# battery_R1_0.net
KiCad netlist of a schematic drawn in EAGLE
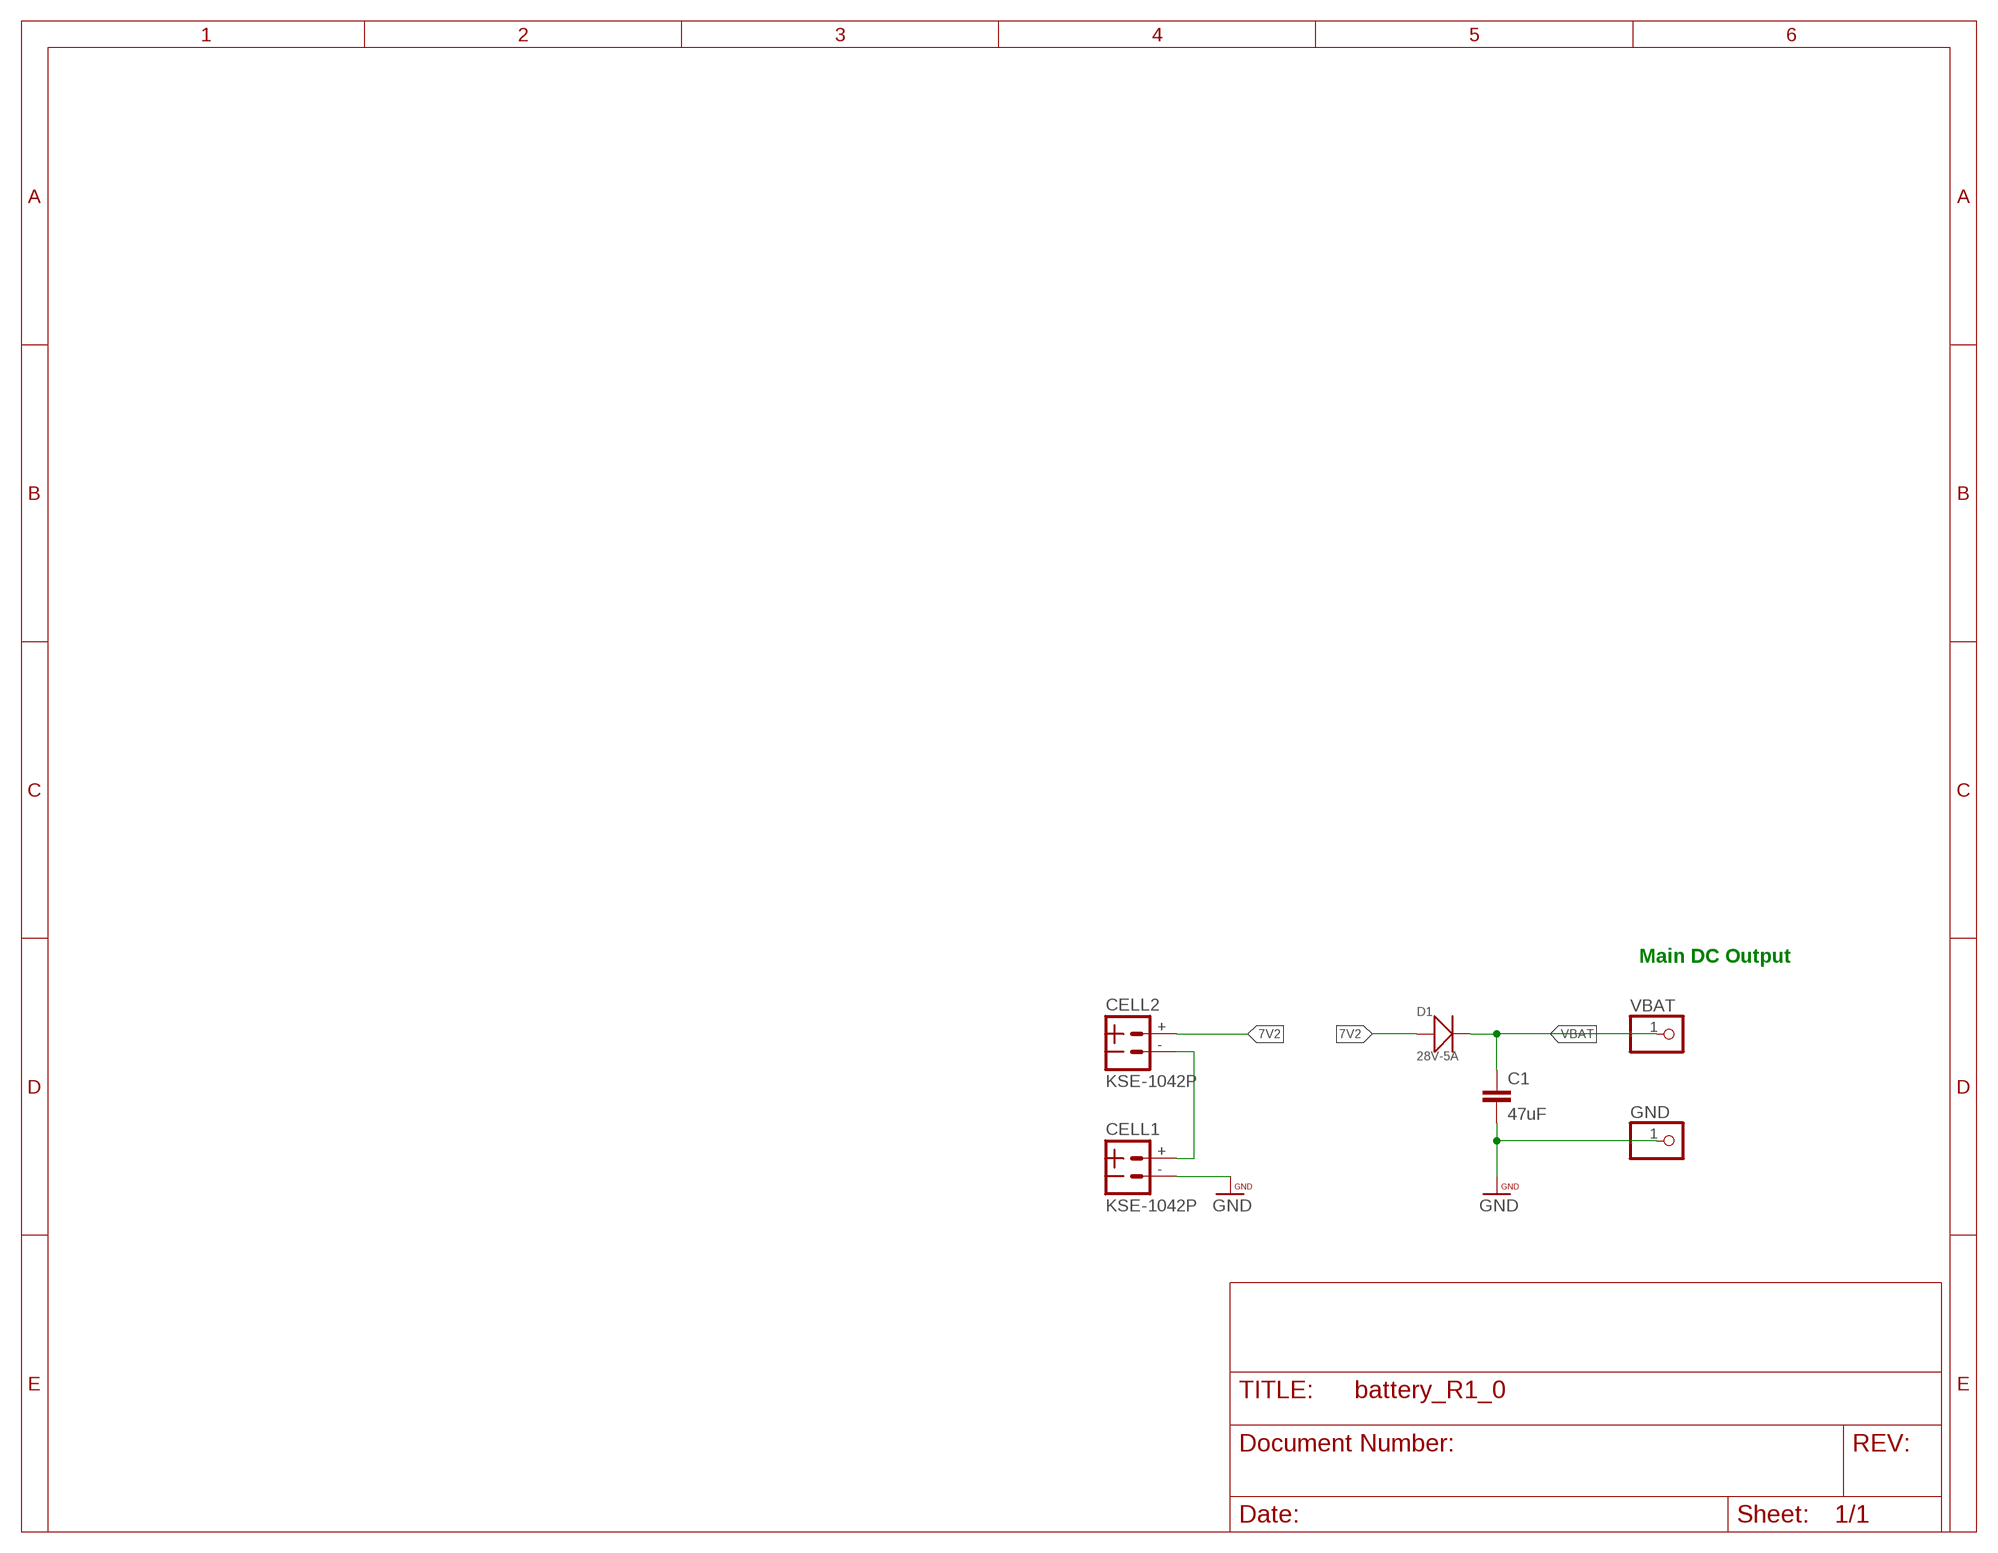
[diagram p0: schematic, sheet 1]

(export (version "E")
  (design (tool "Eeschema 10.0.6"))
  (components
    (comp (ref "C1")
      (value "47uF")
      (footprint "eagle-import:1210")
      (libsource (lib "eagle-import") (part "CAP1210"))
    )
    (comp (ref "CELL1")
      (value "KSE-1042P")
      (footprint "eagle-import:KSE-1042P")
      (libsource (lib "eagle-import") (part "KSE-1042P"))
    )
    (comp (ref "CELL2")
      (value "KSE-1042P")
      (footprint "eagle-import:KSE-1042P")
      (libsource (lib "eagle-import") (part "KSE-1042P"))
    )
    (comp (ref "D1")
      (value "28V-5A")
      (footprint "eagle-import:DO-214AA")
      (fields (field (name "MPN") "SS54B"))
      (libsource (lib "eagle-import") (part "SMD-DIODE-SCHOTTKY-28V-5A(DO-214AA)"))
    )
    (comp (ref "GND")
      (value "WPAD-1-PTH")
      (footprint "eagle-import:WPAD-1-PTH-2.54")
      (libsource (lib "eagle-import") (part "WPAD-1-PTH"))
    )
    (comp (ref "VBAT")
      (value "WPAD-1-PTH")
      (footprint "eagle-import:WPAD-1-PTH-2.54")
      (libsource (lib "eagle-import") (part "WPAD-1-PTH"))
    )
  )
  (nets
    (net (code "1") (name "7V2") (class "Default")
      (node (ref "CELL2") (pin "+") (pinfunction "+_+") (pintype "passive"))
      (node (ref "D1") (pin "+") (pinfunction "+_+") (pintype "passive"))
    )
    (net (code "2") (name "GND") (class "Default")
      (node (ref "C1") (pin "2") (pinfunction "2_2") (pintype "passive"))
      (node (ref "CELL1") (pin "-") (pinfunction "-_-") (pintype "passive"))
      (node (ref "GND") (pin "1") (pinfunction "1_1") (pintype "passive"))
    )
    (net (code "3") (name "Net-(CELL1-Pad+)") (class "Default")
      (node (ref "CELL1") (pin "+") (pinfunction "+_+") (pintype "passive"))
      (node (ref "CELL2") (pin "-") (pinfunction "-_-") (pintype "passive"))
    )
    (net (code "4") (name "VBAT") (class "Default")
      (node (ref "C1") (pin "1") (pinfunction "1_1") (pintype "passive"))
      (node (ref "D1") (pin "-") (pinfunction "-_-") (pintype "passive"))
      (node (ref "VBAT") (pin "1") (pinfunction "1_1") (pintype "passive"))
    )
  )
)
